# DFN6-15-23-A.net
KiCad netlist of a schematic drawn in EAGLE
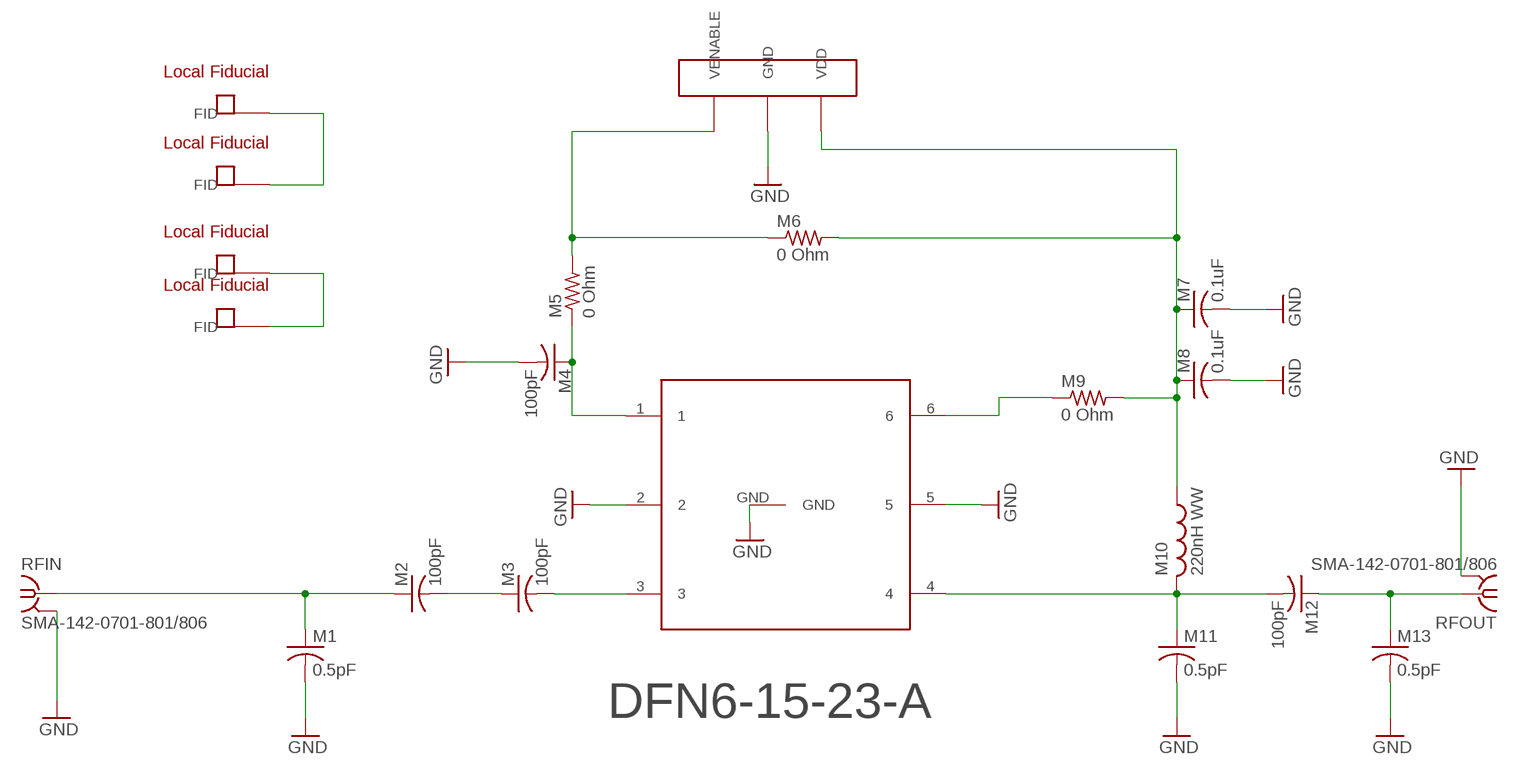
[diagram p0: schematic, sheet 1]

(export (version "E")
  (design (tool "Eeschema 10.0.6"))
  (components
    (comp (ref "FID")
      (value "GRF_LOCAL_FIDUCIAL")
      (footprint "eagle-import:GRF_LOCAL_FIDUCIAL")
      (libsource (lib "eagle-import") (part "GRF_LOCAL_FIDUCIAL"))
    )
    (comp (ref "FID@1")
      (value "GRF_LOCAL_FIDUCIAL")
      (footprint "eagle-import:GRF_LOCAL_FIDUCIAL")
      (libsource (lib "eagle-import") (part "GRF_LOCAL_FIDUCIAL"))
    )
    (comp (ref "J1")
      (value "MOLEX_KK_HEADER_3-PIN_0.100-INCH")
      (footprint "eagle-import:MOLEX_KK_HEADER_3-PIN_0.100-INCH")
      (libsource (lib "eagle-import") (part "MOLEX_KK_HEADER_3-PIN_0.100-INCH"))
    )
    (comp (ref "M1")
      (value "0.5pF")
      (footprint "eagle-import:RCL_C0402_GRF")
      (libsource (lib "eagle-import") (part "RCL_C-US_GRF"))
    )
    (comp (ref "M2")
      (value "100pF")
      (footprint "eagle-import:RCL_C0402_GRF")
      (libsource (lib "eagle-import") (part "RCL_C-US_GRF"))
    )
    (comp (ref "M3")
      (value "100pF")
      (footprint "eagle-import:RCL_C0402_GRF")
      (libsource (lib "eagle-import") (part "RCL_C-US_GRF"))
    )
    (comp (ref "M4")
      (value "100pF")
      (footprint "eagle-import:C0402")
      (libsource (lib "eagle-import") (part "C-USC0402"))
    )
    (comp (ref "M5")
      (value "0 Ohm")
      (footprint "eagle-import:R0402")
      (libsource (lib "eagle-import") (part "R-US_R0402"))
    )
    (comp (ref "M6")
      (value "0 Ohm")
      (footprint "eagle-import:R0402")
      (libsource (lib "eagle-import") (part "R-US_R0402"))
    )
    (comp (ref "M7")
      (value "0.1uF")
      (footprint "eagle-import:C0402")
      (libsource (lib "eagle-import") (part "C-USC0402"))
    )
    (comp (ref "M8")
      (value "0.1uF")
      (footprint "eagle-import:C0402")
      (libsource (lib "eagle-import") (part "C-USC0402"))
    )
    (comp (ref "M9")
      (value "0 Ohm")
      (footprint "eagle-import:R0402")
      (libsource (lib "eagle-import") (part "R-US_R0402"))
    )
    (comp (ref "M10")
      (value "220nH WW")
      (footprint "eagle-import:L0402")
      (libsource (lib "eagle-import") (part "L-USL0402"))
    )
    (comp (ref "M11")
      (value "0.5pF")
      (footprint "eagle-import:RCL_C0402_GRF")
      (libsource (lib "eagle-import") (part "RCL_C-US_GRF"))
    )
    (comp (ref "M12")
      (value "100pF")
      (footprint "eagle-import:RCL_C0402_GRF")
      (libsource (lib "eagle-import") (part "RCL_C-US_GRF"))
    )
    (comp (ref "M13")
      (value "0.5pF")
      (footprint "eagle-import:RCL_C0402_GRF")
      (libsource (lib "eagle-import") (part "RCL_C-US_GRF"))
    )
    (comp (ref "RFIN")
      (value "SMA-142-0701-801/806")
      (footprint "eagle-import:J502-ND-142-0701-801_806")
      (fields (field (name "MF") "JOHNSON COMPONENTS") (field (name "MPN") "142-0701-801"))
      (libsource (lib "eagle-import") (part "SMA-142-0701-801/806"))
    )
    (comp (ref "RFOUT")
      (value "SMA-142-0701-801/806")
      (footprint "eagle-import:J502-ND-142-0701-801_806")
      (fields (field (name "MF") "JOHNSON COMPONENTS") (field (name "MPN") "142-0701-801"))
      (libsource (lib "eagle-import") (part "SMA-142-0701-801/806"))
    )
    (comp (ref "U$1")
      (value "DFN-6_GENERICUPDATED")
      (footprint "eagle-import:DFN-6_1.5X1.5MM_FIXED")
      (libsource (lib "eagle-import") (part "DFN-6_GENERICUPDATED"))
    )
    (comp (ref "U$2")
      (value "GRF_LOCAL_FIDUCIAL")
      (footprint "eagle-import:GRF_LOCAL_FIDUCIAL")
      (libsource (lib "eagle-import") (part "GRF_LOCAL_FIDUCIAL"))
    )
    (comp (ref "U$3")
      (value "GRF_LOCAL_FIDUCIAL")
      (footprint "eagle-import:GRF_LOCAL_FIDUCIAL")
      (libsource (lib "eagle-import") (part "GRF_LOCAL_FIDUCIAL"))
    )
  )
  (nets
    (net (code "1") (name "GND") (class "Default")
      (node (ref "J1") (pin "GND") (pinfunction "GND_GND") (pintype "bidirectional"))
      (node (ref "M1") (pin "2") (pinfunction "2_2") (pintype "passive"))
      (node (ref "M11") (pin "2") (pinfunction "2_2") (pintype "passive"))
      (node (ref "M13") (pin "2") (pinfunction "2_2") (pintype "passive"))
      (node (ref "M4") (pin "2") (pinfunction "2_2") (pintype "passive"))
      (node (ref "M7") (pin "2") (pinfunction "2_2") (pintype "passive"))
      (node (ref "M8") (pin "2") (pinfunction "2_2") (pintype "passive"))
      (node (ref "RFIN") (pin "G@1") (pinfunction "2_G@1") (pintype "passive"))
      (node (ref "RFIN") (pin "G@2") (pinfunction "2_G@2") (pintype "passive"))
      (node (ref "RFIN") (pin "G@3") (pinfunction "2_G@3") (pintype "passive"))
      (node (ref "RFIN") (pin "G@4") (pinfunction "2_G@4") (pintype "passive"))
      (node (ref "RFOUT") (pin "G@1") (pinfunction "2_G@1") (pintype "passive"))
      (node (ref "RFOUT") (pin "G@2") (pinfunction "2_G@2") (pintype "passive"))
      (node (ref "RFOUT") (pin "G@3") (pinfunction "2_G@3") (pintype "passive"))
      (node (ref "RFOUT") (pin "G@4") (pinfunction "2_G@4") (pintype "passive"))
      (node (ref "U$1") (pin "2") (pinfunction "2_2") (pintype "bidirectional"))
      (node (ref "U$1") (pin "5") (pinfunction "5_5") (pintype "bidirectional"))
      (node (ref "U$1") (pin "GND") (pinfunction "GND_GND") (pintype "bidirectional"))
    )
    (net (code "2") (name "Net-(FID-PadFID)") (class "Default")
      (node (ref "FID") (pin "FID") (pinfunction "FID_FID") (pintype "bidirectional"))
      (node (ref "FID@1") (pin "FID") (pinfunction "FID_FID") (pintype "bidirectional"))
    )
    (net (code "3") (name "Net-(J1-PadVDD)") (class "Default")
      (node (ref "J1") (pin "VDD") (pinfunction "VDD_VDD") (pintype "bidirectional"))
      (node (ref "M10") (pin "1") (pinfunction "1_1") (pintype "passive"))
      (node (ref "M6") (pin "2") (pinfunction "2_2") (pintype "passive"))
      (node (ref "M7") (pin "1") (pinfunction "1_1") (pintype "passive"))
      (node (ref "M8") (pin "1") (pinfunction "1_1") (pintype "passive"))
      (node (ref "M9") (pin "2") (pinfunction "2_2") (pintype "passive"))
    )
    (net (code "4") (name "Net-(J1-PadVENABLE)") (class "Default")
      (node (ref "J1") (pin "VENABLE") (pinfunction "VENABLE_VENABLE") (pintype "bidirectional"))
      (node (ref "M5") (pin "2") (pinfunction "2_2") (pintype "passive"))
      (node (ref "M6") (pin "1") (pinfunction "1_1") (pintype "passive"))
    )
    (net (code "5") (name "Net-(M1-Pad1)") (class "Default")
      (node (ref "M1") (pin "1") (pinfunction "1_1") (pintype "passive"))
      (node (ref "M2") (pin "1") (pinfunction "1_1") (pintype "passive"))
      (node (ref "RFIN") (pin "1") (pinfunction "1_1") (pintype "passive"))
    )
    (net (code "6") (name "Net-(M2-Pad2)") (class "Default")
      (node (ref "M2") (pin "2") (pinfunction "2_2") (pintype "passive"))
      (node (ref "M3") (pin "1") (pinfunction "1_1") (pintype "passive"))
    )
    (net (code "7") (name "Net-(M3-Pad2)") (class "Default")
      (node (ref "M3") (pin "2") (pinfunction "2_2") (pintype "passive"))
      (node (ref "U$1") (pin "3") (pinfunction "3_3") (pintype "bidirectional"))
    )
    (net (code "8") (name "Net-(M4-Pad1)") (class "Default")
      (node (ref "M4") (pin "1") (pinfunction "1_1") (pintype "passive"))
      (node (ref "M5") (pin "1") (pinfunction "1_1") (pintype "passive"))
      (node (ref "U$1") (pin "1") (pinfunction "1_1") (pintype "bidirectional"))
    )
    (net (code "9") (name "Net-(M9-Pad1)") (class "Default")
      (node (ref "M9") (pin "1") (pinfunction "1_1") (pintype "passive"))
      (node (ref "U$1") (pin "6") (pinfunction "6_6") (pintype "bidirectional"))
    )
    (net (code "10") (name "Net-(M10-Pad2)") (class "Default")
      (node (ref "M10") (pin "2") (pinfunction "2_2") (pintype "passive"))
      (node (ref "M11") (pin "1") (pinfunction "1_1") (pintype "passive"))
      (node (ref "M12") (pin "2") (pinfunction "2_2") (pintype "passive"))
      (node (ref "U$1") (pin "4") (pinfunction "4_4") (pintype "bidirectional"))
    )
    (net (code "11") (name "Net-(M12-Pad1)") (class "Default")
      (node (ref "M12") (pin "1") (pinfunction "1_1") (pintype "passive"))
      (node (ref "M13") (pin "1") (pinfunction "1_1") (pintype "passive"))
      (node (ref "RFOUT") (pin "1") (pinfunction "1_1") (pintype "passive"))
    )
    (net (code "12") (name "Net-(U$2-PadFID)") (class "Default")
      (node (ref "U$2") (pin "FID") (pinfunction "FID_FID") (pintype "bidirectional"))
      (node (ref "U$3") (pin "FID") (pinfunction "FID_FID") (pintype "bidirectional"))
    )
  )
)
